# Track_em_V0_2.net
KiCad netlist of a schematic drawn in EAGLE
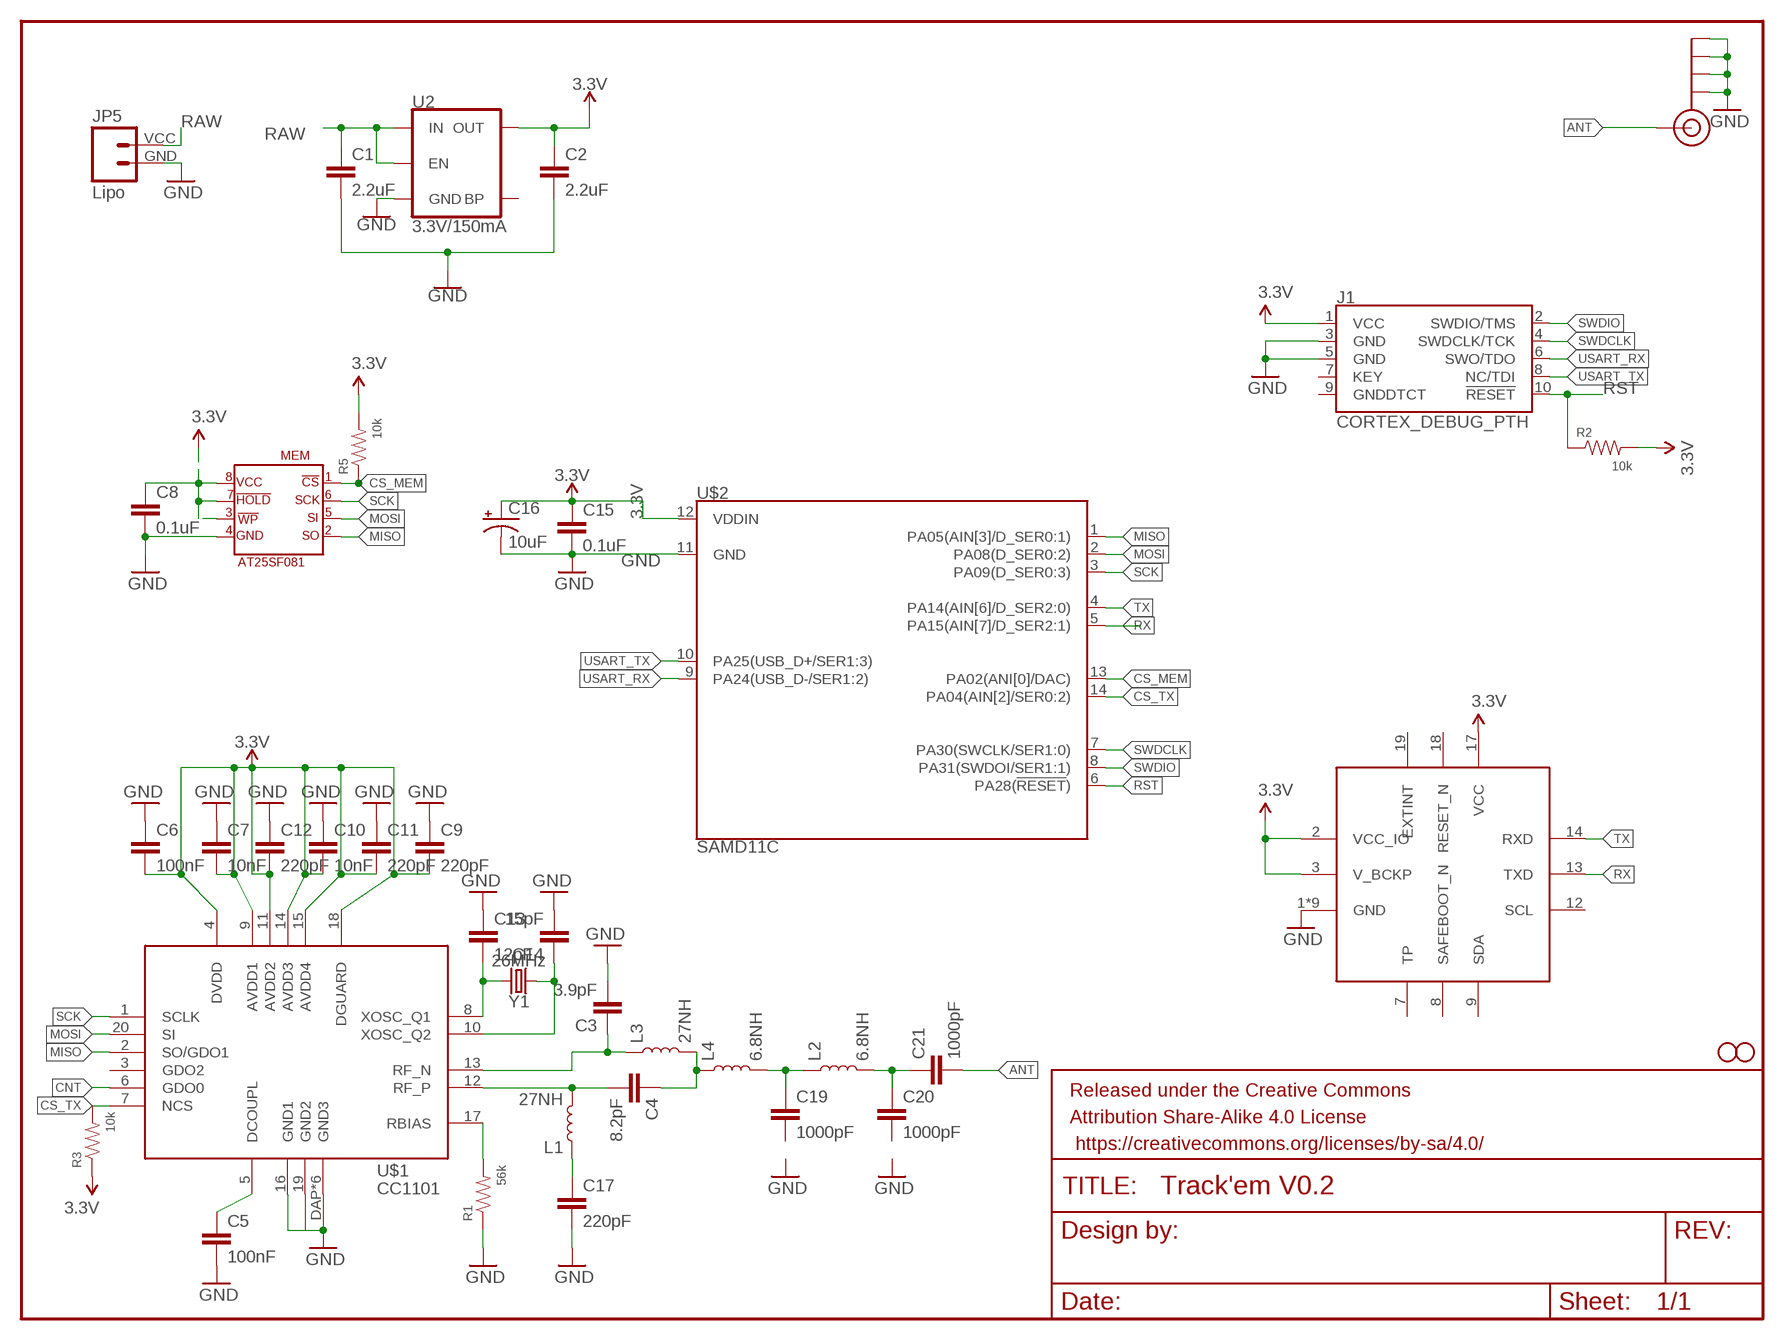
[diagram p0: schematic, sheet 1]

(export (version "E")
  (design (tool "Eeschema 10.0.6"))
  (components
    (comp (ref "C1")
      (value "2.2uF")
      (footprint "eagle-import:0603")
      (libsource (lib "eagle-import") (part "2.2UF-0603-10V-20%"))
    )
    (comp (ref "C2")
      (value "2.2uF")
      (footprint "eagle-import:0603")
      (libsource (lib "eagle-import") (part "2.2UF-0603-10V-20%"))
    )
    (comp (ref "C3")
      (value "3.9pF")
      (footprint "eagle-import:0402")
      (libsource (lib "eagle-import") (part "0.1UF-0402-16V-10%"))
    )
    (comp (ref "C4")
      (value "8.2pF")
      (footprint "eagle-import:0402")
      (libsource (lib "eagle-import") (part "0.1UF-0402-16V-10%"))
    )
    (comp (ref "C5")
      (value "100nF")
      (footprint "eagle-import:0402")
      (libsource (lib "eagle-import") (part "0.1UF-0402-16V-10%"))
    )
    (comp (ref "C6")
      (value "100nF")
      (footprint "eagle-import:0402")
      (libsource (lib "eagle-import") (part "0.1UF-0402-16V-10%"))
    )
    (comp (ref "C7")
      (value "10nF")
      (footprint "eagle-import:0402")
      (libsource (lib "eagle-import") (part "0.1UF-0402-16V-10%"))
    )
    (comp (ref "C8")
      (value "0.1uF")
      (footprint "eagle-import:0402")
      (libsource (lib "eagle-import") (part "0.1UF-0402-16V-10%"))
    )
    (comp (ref "C9")
      (value "220pF")
      (footprint "eagle-import:0402")
      (libsource (lib "eagle-import") (part "0.1UF-0402-16V-10%"))
    )
    (comp (ref "C10")
      (value "10nF")
      (footprint "eagle-import:0402")
      (libsource (lib "eagle-import") (part "0.1UF-0402-16V-10%"))
    )
    (comp (ref "C11")
      (value "220pF")
      (footprint "eagle-import:0402")
      (libsource (lib "eagle-import") (part "0.1UF-0402-16V-10%"))
    )
    (comp (ref "C12")
      (value "220pF")
      (footprint "eagle-import:0402")
      (libsource (lib "eagle-import") (part "0.1UF-0402-16V-10%"))
    )
    (comp (ref "C13")
      (value "12pF")
      (footprint "eagle-import:0402")
      (libsource (lib "eagle-import") (part "0.1UF-0402-16V-10%"))
    )
    (comp (ref "C14")
      (value "15pF")
      (footprint "eagle-import:0402")
      (libsource (lib "eagle-import") (part "0.1UF-0402-16V-10%"))
    )
    (comp (ref "C15")
      (value "0.1uF")
      (footprint "eagle-import:0402")
      (libsource (lib "eagle-import") (part "0.1UF-0402-16V-10%"))
    )
    (comp (ref "C16")
      (value "10uF")
      (footprint "eagle-import:0603-POL")
      (libsource (lib "eagle-import") (part "10UF-6.3V-20%(0603)(TANT){dblquote}"))
    )
    (comp (ref "C17")
      (value "220pF")
      (footprint "eagle-import:0402")
      (libsource (lib "eagle-import") (part "0.1UF-0402-16V-10%"))
    )
    (comp (ref "C19")
      (value "1000pF")
      (footprint "eagle-import:0402")
      (libsource (lib "eagle-import") (part "0.1UF-0402-16V-10%"))
    )
    (comp (ref "C20")
      (value "1000pF")
      (footprint "eagle-import:0402")
      (libsource (lib "eagle-import") (part "0.1UF-0402-16V-10%"))
    )
    (comp (ref "C21")
      (value "1000pF")
      (footprint "eagle-import:0402")
      (libsource (lib "eagle-import") (part "0.1UF-0402-16V-10%"))
    )
    (comp (ref "FRAME1")
      (value "FRAME-LETTERNO_PACKAGE")
      (footprint "eagle-import:DUMMY")
      (fields (field (name "DESIGNER") "Nobody"))
      (libsource (lib "eagle-import") (part "FRAME-LETTERNO_PACKAGE"))
    )
    (comp (ref "H1")
      (value "STAND-OFFTIGHT")
      (footprint "eagle-import:STAND-OFF-TIGHT")
      (libsource (lib "eagle-import") (part "STAND-OFFTIGHT"))
    )
    (comp (ref "H2")
      (value "STAND-OFFTIGHT")
      (footprint "eagle-import:STAND-OFF-TIGHT")
      (libsource (lib "eagle-import") (part "STAND-OFFTIGHT"))
    )
    (comp (ref "IC1")
      (value "SAM-M8Q")
      (footprint "eagle-import:SAM-M8Q")
      (libsource (lib "eagle-import") (part "SAM-M8Q"))
    )
    (comp (ref "J$1")
      (value "SMA_EDGE")
      (footprint "eagle-import:SMA-EDGE")
      (libsource (lib "eagle-import") (part "SMA_EDGE"))
    )
    (comp (ref "J1")
      (value "CORTEX_DEBUG_PTH")
      (footprint "eagle-import:2X5-PTH-1.27MM")
      (libsource (lib "eagle-import") (part "CORTEX_DEBUG_PTH"))
    )
    (comp (ref "JP5")
      (value "Lipo")
      (footprint "eagle-import:JST-2-SMD-VERT")
      (libsource (lib "eagle-import") (part "M024UCON-15767"))
    )
    (comp (ref "L1")
      (value "27NH")
      (footprint "eagle-import:0402")
      (libsource (lib "eagle-import") (part "INDUCTOR-0402-3.9NH"))
    )
    (comp (ref "L2")
      (value "6.8NH")
      (footprint "eagle-import:0402")
      (libsource (lib "eagle-import") (part "INDUCTOR-0402-3.9NH"))
    )
    (comp (ref "L3")
      (value "27NH")
      (footprint "eagle-import:0402")
      (libsource (lib "eagle-import") (part "INDUCTOR-0402-3.9NH"))
    )
    (comp (ref "L4")
      (value "6.8NH")
      (footprint "eagle-import:0402")
      (libsource (lib "eagle-import") (part "INDUCTOR-0402-3.9NH"))
    )
    (comp (ref "MEM")
      (value "AT25SF081")
      (footprint "eagle-import:AT25SF081")
      (libsource (lib "eagle-import") (part "AT25SF081"))
    )
    (comp (ref "R1")
      (value "56k")
      (footprint "eagle-import:0402")
      (libsource (lib "eagle-import") (part "RESISTOR0402"))
    )
    (comp (ref "R2")
      (value "10k")
      (footprint "eagle-import:0402")
      (libsource (lib "eagle-import") (part "RESISTOR0402"))
    )
    (comp (ref "R3")
      (value "10k")
      (footprint "eagle-import:0402")
      (libsource (lib "eagle-import") (part "RESISTOR0402"))
    )
    (comp (ref "R5")
      (value "10k")
      (footprint "eagle-import:0402")
      (libsource (lib "eagle-import") (part "RESISTOR0402"))
    )
    (comp (ref "U$1")
      (value "CC1101")
      (footprint "eagle-import:CC1101")
      (libsource (lib "eagle-import") (part "CC1101"))
    )
    (comp (ref "U$2")
      (value "SAMD11C")
      (footprint "eagle-import:SAMD11C")
      (libsource (lib "eagle-import") (part "SAMD11C"))
    )
    (comp (ref "U2")
      (value "3.3V/150mA")
      (footprint "eagle-import:SOT23-5")
      (libsource (lib "eagle-import") (part "V_REG_MIC52053.3V"))
    )
    (comp (ref "Y1")
      (value "26MHz")
      (footprint "eagle-import:CRYSTAL-SMD-3.2X2.5MM")
      (libsource (lib "eagle-import") (part "CRYSTALSMD-3.2X2.5"))
    )
  )
  (nets
    (net (code "1") (name "/RAW") (class "Default")
      (node (ref "C1") (pin "1") (pinfunction "1_1") (pintype "passive"))
      (node (ref "JP5") (pin "VCC") (pinfunction "2_VCC") (pintype "passive"))
      (node (ref "U2") (pin "1") (pinfunction "IN_1") (pintype "input"))
      (node (ref "U2") (pin "3") (pinfunction "EN_3") (pintype "input"))
    )
    (net (code "2") (name "3.3V") (class "Default")
      (node (ref "C10") (pin "2") (pinfunction "2_2") (pintype "passive"))
      (node (ref "C11") (pin "2") (pinfunction "2_2") (pintype "passive"))
      (node (ref "C12") (pin "2") (pinfunction "2_2") (pintype "passive"))
      (node (ref "C15") (pin "1") (pinfunction "1_1") (pintype "passive"))
      (node (ref "C16") (pin "A") (pinfunction "+_A") (pintype "passive"))
      (node (ref "C2") (pin "1") (pinfunction "1_1") (pintype "passive"))
      (node (ref "C6") (pin "2") (pinfunction "2_2") (pintype "passive"))
      (node (ref "C7") (pin "2") (pinfunction "2_2") (pintype "passive"))
      (node (ref "C8") (pin "1") (pinfunction "1_1") (pintype "passive"))
      (node (ref "C9") (pin "2") (pinfunction "2_2") (pintype "passive"))
      (node (ref "IC1") (pin "17") (pinfunction "VCC_17") (pintype "bidirectional"))
      (node (ref "IC1") (pin "2") (pinfunction "VCC_IO_2") (pintype "bidirectional"))
      (node (ref "IC1") (pin "3") (pinfunction "V_BCKP_3") (pintype "bidirectional"))
      (node (ref "J1") (pin "1") (pinfunction "VCC_1") (pintype "bidirectional"))
      (node (ref "MEM") (pin "!HOLD") (pinfunction "~{HOLD}_!HOLD") (pintype "bidirectional"))
      (node (ref "MEM") (pin "!WP") (pinfunction "~{WP}_!WP") (pintype "bidirectional"))
      (node (ref "MEM") (pin "VCC") (pinfunction "VCC_VCC") (pintype "bidirectional"))
      (node (ref "R2") (pin "2") (pinfunction "2_2") (pintype "passive"))
      (node (ref "R3") (pin "1") (pinfunction "1_1") (pintype "passive"))
      (node (ref "R5") (pin "2") (pinfunction "2_2") (pintype "passive"))
      (node (ref "U$1") (pin "11") (pinfunction "AVDD2_11") (pintype "bidirectional"))
      (node (ref "U$1") (pin "14") (pinfunction "AVDD3_14") (pintype "bidirectional"))
      (node (ref "U$1") (pin "15") (pinfunction "AVDD4_15") (pintype "bidirectional"))
      (node (ref "U$1") (pin "18") (pinfunction "DGUARD_18") (pintype "bidirectional"))
      (node (ref "U$1") (pin "4") (pinfunction "DVDD_4") (pintype "bidirectional"))
      (node (ref "U$1") (pin "9") (pinfunction "AVDD1_9") (pintype "bidirectional"))
      (node (ref "U$2") (pin "12") (pinfunction "VDDIN_12") (pintype "bidirectional"))
      (node (ref "U2") (pin "5") (pinfunction "OUT_5") (pintype "passive"))
    )
    (net (code "3") (name "ANT") (class "Default")
      (node (ref "C21") (pin "2") (pinfunction "2_2") (pintype "passive"))
      (node (ref "J$1") (pin "SIG") (pinfunction "SIGNAL_SIG") (pintype "bidirectional"))
    )
    (net (code "4") (name "CNT") (class "Default")
      (node (ref "U$1") (pin "6") (pinfunction "GDO0_6") (pintype "bidirectional"))
    )
    (net (code "5") (name "CS_MEM") (class "Default")
      (node (ref "MEM") (pin "!CS") (pinfunction "~{CS}_!CS") (pintype "bidirectional"))
      (node (ref "R5") (pin "1") (pinfunction "1_1") (pintype "passive"))
      (node (ref "U$2") (pin "13") (pinfunction "PA02(ANI[0]/DAC)_13") (pintype "bidirectional"))
    )
    (net (code "6") (name "CS_TX") (class "Default")
      (node (ref "R3") (pin "2") (pinfunction "2_2") (pintype "passive"))
      (node (ref "U$1") (pin "7") (pinfunction "NCS_7") (pintype "bidirectional"))
      (node (ref "U$2") (pin "14") (pinfunction "PA04(AIN[2]/SER0:2)_14") (pintype "bidirectional"))
    )
    (net (code "7") (name "GND") (class "Default")
      (node (ref "C1") (pin "2") (pinfunction "2_2") (pintype "passive"))
      (node (ref "C10") (pin "1") (pinfunction "1_1") (pintype "passive"))
      (node (ref "C11") (pin "1") (pinfunction "1_1") (pintype "passive"))
      (node (ref "C12") (pin "1") (pinfunction "1_1") (pintype "passive"))
      (node (ref "C13") (pin "1") (pinfunction "1_1") (pintype "passive"))
      (node (ref "C14") (pin "2") (pinfunction "2_2") (pintype "passive"))
      (node (ref "C15") (pin "2") (pinfunction "2_2") (pintype "passive"))
      (node (ref "C16") (pin "K") (pinfunction "-_K") (pintype "passive"))
      (node (ref "C17") (pin "2") (pinfunction "2_2") (pintype "passive"))
      (node (ref "C2") (pin "2") (pinfunction "2_2") (pintype "passive"))
      (node (ref "C3") (pin "2") (pinfunction "2_2") (pintype "passive"))
      (node (ref "C5") (pin "2") (pinfunction "2_2") (pintype "passive"))
      (node (ref "C6") (pin "1") (pinfunction "1_1") (pintype "passive"))
      (node (ref "C7") (pin "1") (pinfunction "1_1") (pintype "passive"))
      (node (ref "C8") (pin "2") (pinfunction "2_2") (pintype "passive"))
      (node (ref "C9") (pin "1") (pinfunction "1_1") (pintype "passive"))
      (node (ref "IC1") (pin "1") (pinfunction "GND_1") (pintype "bidirectional"))
      (node (ref "IC1") (pin "10") (pinfunction "GND_10") (pintype "bidirectional"))
      (node (ref "IC1") (pin "11") (pinfunction "GND_11") (pintype "bidirectional"))
      (node (ref "IC1") (pin "15") (pinfunction "GND_15") (pintype "bidirectional"))
      (node (ref "IC1") (pin "16") (pinfunction "GND_16") (pintype "bidirectional"))
      (node (ref "IC1") (pin "20") (pinfunction "GND_20") (pintype "bidirectional"))
      (node (ref "IC1") (pin "4") (pinfunction "GND_4") (pintype "bidirectional"))
      (node (ref "IC1") (pin "5") (pinfunction "GND_5") (pintype "bidirectional"))
      (node (ref "IC1") (pin "6") (pinfunction "GND_6") (pintype "bidirectional"))
      (node (ref "J$1") (pin "GND@0") (pinfunction "GND_GND@0") (pintype "bidirectional"))
      (node (ref "J$1") (pin "GND@1") (pinfunction "GND_GND@1") (pintype "bidirectional"))
      (node (ref "J$1") (pin "GND@2") (pinfunction "GND_GND@2") (pintype "bidirectional"))
      (node (ref "J$1") (pin "GND@3") (pinfunction "GND_GND@3") (pintype "bidirectional"))
      (node (ref "J1") (pin "3") (pinfunction "GND_3") (pintype "bidirectional"))
      (node (ref "J1") (pin "5") (pinfunction "GND_5") (pintype "bidirectional"))
      (node (ref "JP5") (pin "GND") (pinfunction "1_GND") (pintype "passive"))
      (node (ref "MEM") (pin "GND") (pinfunction "GND_GND") (pintype "bidirectional"))
      (node (ref "R1") (pin "1") (pinfunction "1_1") (pintype "passive"))
      (node (ref "U$1") (pin "16") (pinfunction "GND1_16") (pintype "bidirectional"))
      (node (ref "U$1") (pin "19") (pinfunction "GND2_19") (pintype "bidirectional"))
      (node (ref "U$1") (pin "DAP") (pinfunction "GND3_DAP") (pintype "bidirectional"))
      (node (ref "U$1") (pin "P$1") (pinfunction "GND3_P$1") (pintype "bidirectional"))
      (node (ref "U$1") (pin "P$2") (pinfunction "GND3_P$2") (pintype "bidirectional"))
      (node (ref "U$1") (pin "P$3") (pinfunction "GND3_P$3") (pintype "bidirectional"))
      (node (ref "U$1") (pin "P$4") (pinfunction "GND3_P$4") (pintype "bidirectional"))
      (node (ref "U$1") (pin "P$5") (pinfunction "GND3_P$5") (pintype "bidirectional"))
      (node (ref "U$2") (pin "11") (pinfunction "GND_11") (pintype "bidirectional"))
      (node (ref "U2") (pin "2") (pinfunction "GND_2") (pintype "input"))
    )
    (net (code "8") (name "MISO") (class "Default")
      (node (ref "MEM") (pin "SO") (pinfunction "SO_SO") (pintype "bidirectional"))
      (node (ref "U$1") (pin "2") (pinfunction "SO/GDO1_2") (pintype "bidirectional"))
      (node (ref "U$2") (pin "1") (pinfunction "PA05(AIN[3]/D_SER0:1)_1") (pintype "bidirectional"))
    )
    (net (code "9") (name "MOSI") (class "Default")
      (node (ref "MEM") (pin "SI") (pinfunction "SI_SI") (pintype "bidirectional"))
      (node (ref "U$1") (pin "20") (pinfunction "SI_20") (pintype "bidirectional"))
      (node (ref "U$2") (pin "2") (pinfunction "PA08(D_SER0:2)_2") (pintype "bidirectional"))
    )
    (net (code "10") (name "Net-(C4-Pad1)") (class "Default")
      (node (ref "C4") (pin "1") (pinfunction "1_1") (pintype "passive"))
      (node (ref "L3") (pin "2") (pinfunction "2_2") (pintype "passive"))
      (node (ref "L4") (pin "1") (pinfunction "1_1") (pintype "passive"))
    )
    (net (code "11") (name "Net-(C17-Pad1)") (class "Default")
      (node (ref "C17") (pin "1") (pinfunction "1_1") (pintype "passive"))
      (node (ref "L1") (pin "1") (pinfunction "1_1") (pintype "passive"))
    )
    (net (code "12") (name "Net-(C19-Pad1)") (class "Default")
      (node (ref "C19") (pin "1") (pinfunction "1_1") (pintype "passive"))
      (node (ref "L2") (pin "1") (pinfunction "1_1") (pintype "passive"))
      (node (ref "L4") (pin "2") (pinfunction "2_2") (pintype "passive"))
    )
    (net (code "13") (name "Net-(C20-Pad1)") (class "Default")
      (node (ref "C20") (pin "1") (pinfunction "1_1") (pintype "passive"))
      (node (ref "C21") (pin "1") (pinfunction "1_1") (pintype "passive"))
      (node (ref "L2") (pin "2") (pinfunction "2_2") (pintype "passive"))
    )
    (net (code "14") (name "Net-(U$1-DCOUPL)") (class "Default")
      (node (ref "C5") (pin "1") (pinfunction "1_1") (pintype "passive"))
      (node (ref "U$1") (pin "5") (pinfunction "DCOUPL_5") (pintype "bidirectional"))
    )
    (net (code "15") (name "Net-(U$1-RBIAS)") (class "Default")
      (node (ref "R1") (pin "2") (pinfunction "2_2") (pintype "passive"))
      (node (ref "U$1") (pin "17") (pinfunction "RBIAS_17") (pintype "bidirectional"))
    )
    (net (code "16") (name "Net-(U$1-RF_N)") (class "Default")
      (node (ref "C3") (pin "1") (pinfunction "1_1") (pintype "passive"))
      (node (ref "L3") (pin "1") (pinfunction "1_1") (pintype "passive"))
      (node (ref "U$1") (pin "13") (pinfunction "RF_N_13") (pintype "bidirectional"))
    )
    (net (code "17") (name "Net-(U$1-RF_P)") (class "Default")
      (node (ref "C4") (pin "2") (pinfunction "2_2") (pintype "passive"))
      (node (ref "L1") (pin "2") (pinfunction "2_2") (pintype "passive"))
      (node (ref "U$1") (pin "12") (pinfunction "RF_P_12") (pintype "bidirectional"))
    )
    (net (code "18") (name "Net-(U$1-XOSC_Q1)") (class "Default")
      (node (ref "C13") (pin "2") (pinfunction "2_2") (pintype "passive"))
      (node (ref "U$1") (pin "8") (pinfunction "XOSC_Q1_8") (pintype "bidirectional"))
      (node (ref "Y1") (pin "3") (pinfunction "2_3") (pintype "passive"))
    )
    (net (code "19") (name "Net-(U$1-XOSC_Q2)") (class "Default")
      (node (ref "C14") (pin "1") (pinfunction "1_1") (pintype "passive"))
      (node (ref "U$1") (pin "10") (pinfunction "XOSC_Q2_10") (pintype "bidirectional"))
      (node (ref "Y1") (pin "1") (pinfunction "1_1") (pintype "passive"))
    )
    (net (code "20") (name "RST") (class "Default")
      (node (ref "J1") (pin "10") (pinfunction "~{RESET}_10") (pintype "bidirectional"))
      (node (ref "R2") (pin "1") (pinfunction "1_1") (pintype "passive"))
      (node (ref "U$2") (pin "6") (pinfunction "PA28(~{RESET})_6") (pintype "bidirectional"))
    )
    (net (code "21") (name "RX") (class "Default")
      (node (ref "IC1") (pin "13") (pinfunction "TXD_13") (pintype "bidirectional"))
      (node (ref "U$2") (pin "5") (pinfunction "PA15(AIN[7]/D_SER2:1)_5") (pintype "bidirectional"))
    )
    (net (code "22") (name "SCK") (class "Default")
      (node (ref "MEM") (pin "SCK") (pinfunction "SCK_SCK") (pintype "bidirectional"))
      (node (ref "U$1") (pin "1") (pinfunction "SCLK_1") (pintype "bidirectional"))
      (node (ref "U$2") (pin "3") (pinfunction "PA09(D_SER0:3)_3") (pintype "bidirectional"))
    )
    (net (code "23") (name "SWDCLK") (class "Default")
      (node (ref "J1") (pin "4") (pinfunction "SWDCLK/TCK_4") (pintype "bidirectional"))
      (node (ref "U$2") (pin "7") (pinfunction "PA30(SWCLK/SER1:0)_7") (pintype "bidirectional"))
    )
    (net (code "24") (name "SWDIO") (class "Default")
      (node (ref "J1") (pin "2") (pinfunction "SWDIO/TMS_2") (pintype "bidirectional"))
      (node (ref "U$2") (pin "8") (pinfunction "PA31(SWDOI/SER1:1)_8") (pintype "bidirectional"))
    )
    (net (code "25") (name "TX") (class "Default")
      (node (ref "IC1") (pin "14") (pinfunction "RXD_14") (pintype "bidirectional"))
      (node (ref "U$2") (pin "4") (pinfunction "PA14(AIN[6]/D_SER2:0)_4") (pintype "bidirectional"))
    )
    (net (code "26") (name "USART_RX") (class "Default")
      (node (ref "J1") (pin "6") (pinfunction "SWO/TDO_6") (pintype "bidirectional"))
      (node (ref "U$2") (pin "9") (pinfunction "PA24(USB_D-/SER1:2)_9") (pintype "bidirectional"))
    )
    (net (code "27") (name "USART_TX") (class "Default")
      (node (ref "J1") (pin "8") (pinfunction "NC/TDI_8") (pintype "bidirectional"))
      (node (ref "U$2") (pin "10") (pinfunction "PA25(USB_D+/SER1:3)_10") (pintype "bidirectional"))
    )
    (net (code "28") (name "unconnected-(C19-Pad2)") (class "Default")
      (node (ref "C19") (pin "2") (pinfunction "2_2") (pintype "passive"))
    )
    (net (code "29") (name "unconnected-(C20-Pad2)") (class "Default")
      (node (ref "C20") (pin "2") (pinfunction "2_2") (pintype "passive"))
    )
    (net (code "30") (name "unconnected-(IC1-EXTINT-Pad19)") (class "Default")
      (node (ref "IC1") (pin "19") (pinfunction "EXTINT_19") (pintype "bidirectional"))
    )
    (net (code "31") (name "unconnected-(IC1-RESET_N-Pad18)") (class "Default")
      (node (ref "IC1") (pin "18") (pinfunction "RESET_N_18") (pintype "bidirectional"))
    )
    (net (code "32") (name "unconnected-(IC1-SAFEBOOT_N-Pad8)") (class "Default")
      (node (ref "IC1") (pin "8") (pinfunction "SAFEBOOT_N_8") (pintype "bidirectional"))
    )
    (net (code "33") (name "unconnected-(IC1-SCL-Pad12)") (class "Default")
      (node (ref "IC1") (pin "12") (pinfunction "SCL_12") (pintype "bidirectional"))
    )
    (net (code "34") (name "unconnected-(IC1-SDA-Pad9)") (class "Default")
      (node (ref "IC1") (pin "9") (pinfunction "SDA_9") (pintype "bidirectional"))
    )
    (net (code "35") (name "unconnected-(IC1-TP-Pad7)") (class "Default")
      (node (ref "IC1") (pin "7") (pinfunction "TP_7") (pintype "bidirectional"))
    )
    (net (code "36") (name "unconnected-(J1-GNDDTCT-Pad9)") (class "Default")
      (node (ref "J1") (pin "9") (pinfunction "GNDDTCT_9") (pintype "bidirectional"))
    )
    (net (code "37") (name "unconnected-(J1-KEY-Pad7)") (class "Default")
      (node (ref "J1") (pin "7") (pinfunction "KEY_7") (pintype "bidirectional"))
    )
    (net (code "38") (name "unconnected-(U$1-GDO2-Pad3)") (class "Default")
      (node (ref "U$1") (pin "3") (pinfunction "GDO2_3") (pintype "bidirectional"))
    )
    (net (code "39") (name "unconnected-(U2-BP-Pad4)") (class "Default")
      (node (ref "U2") (pin "4") (pinfunction "BP_4") (pintype "input"))
    )
  )
)
